# FourKeysKeyboard.net
KiCad netlist of a schematic drawn in Altium Designer
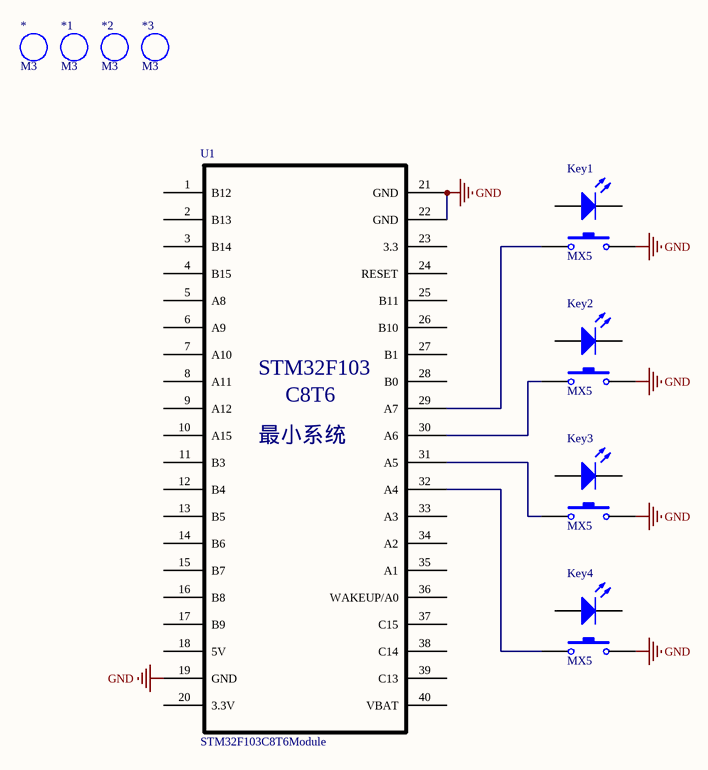
[diagram p0: FourKeysKeyboard.SchDoc]

(export (version "E")
  (design (tool "Eeschema 10.0.6"))
  (components
    (comp (ref "*")
      (value "M3")
      (footprint "M3 125X200")
      (description "铜柱孔")
      (fields (field (name "版权归属") "源创客"))
      (libsource (lib "未分类器件") (part "M3"))
    )
    (comp (ref "*1")
      (value "M3")
      (footprint "M3 125X200")
      (description "铜柱孔")
      (fields (field (name "版权归属") "源创客"))
      (libsource (lib "未分类器件") (part "M3"))
    )
    (comp (ref "*2")
      (value "M3")
      (footprint "M3 125X200")
      (description "铜柱孔")
      (fields (field (name "版权归属") "源创客"))
      (libsource (lib "未分类器件") (part "M3"))
    )
    (comp (ref "*3")
      (value "M3")
      (footprint "M3 125X200")
      (description "铜柱孔")
      (fields (field (name "版权归属") "源创客"))
      (libsource (lib "未分类器件") (part "M3"))
    )
    (comp (ref "Key1")
      (value "MX5")
      (footprint "LSW DIP-CHERRY")
      (libsource (lib "Multicoloredstone's_SW_and_Connector_Lib") (part "Cherry_Key_withLED"))
    )
    (comp (ref "Key2")
      (value "MX5")
      (footprint "LSW DIP-CHERRY")
      (libsource (lib "Multicoloredstone's_SW_and_Connector_Lib") (part "Cherry_Key_withLED"))
    )
    (comp (ref "Key3")
      (value "MX5")
      (footprint "LSW DIP-CHERRY")
      (libsource (lib "Multicoloredstone's_SW_and_Connector_Lib") (part "Cherry_Key_withLED"))
    )
    (comp (ref "Key4")
      (value "MX5")
      (footprint "LSW DIP-CHERRY")
      (libsource (lib "Multicoloredstone's_SW_and_Connector_Lib") (part "Cherry_Key_withLED"))
    )
    (comp (ref "U1")
      (value "STM32F103C8T6Module")
      (footprint "STM32F103C8T6_Module")
      (libsource (lib "Multicoloredstone's_Module_Lib") (part "STM32F103C8T6Module"))
    )
  )
  (nets
    (net (code "1") (name "GND") (class "Default")
      (node (ref "Key1") (pin "2") (pinfunction "2_2") (pintype "passive"))
      (node (ref "Key2") (pin "2") (pinfunction "2_2") (pintype "passive"))
      (node (ref "Key3") (pin "2") (pinfunction "2_2") (pintype "passive"))
      (node (ref "Key4") (pin "2") (pinfunction "2_2") (pintype "passive"))
      (node (ref "U1") (pin "19") (pinfunction "GND_19") (pintype "passive"))
      (node (ref "U1") (pin "21") (pinfunction "GND_21") (pintype "passive"))
      (node (ref "U1") (pin "22") (pinfunction "GND_22") (pintype "passive"))
    )
    (net (code "2") (name "Net-(U1-A4)") (class "Default")
      (node (ref "Key4") (pin "1") (pinfunction "1_1") (pintype "passive"))
      (node (ref "U1") (pin "32") (pinfunction "A4_32") (pintype "passive"))
    )
    (net (code "3") (name "Net-(U1-A5)") (class "Default")
      (node (ref "Key3") (pin "1") (pinfunction "1_1") (pintype "passive"))
      (node (ref "U1") (pin "31") (pinfunction "A5_31") (pintype "passive"))
    )
    (net (code "4") (name "Net-(U1-A6)") (class "Default")
      (node (ref "Key2") (pin "1") (pinfunction "1_1") (pintype "passive"))
      (node (ref "U1") (pin "30") (pinfunction "A6_30") (pintype "passive"))
    )
    (net (code "5") (name "Net-(U1-A7)") (class "Default")
      (node (ref "Key1") (pin "1") (pinfunction "1_1") (pintype "passive"))
      (node (ref "U1") (pin "29") (pinfunction "A7_29") (pintype "passive"))
    )
    (net (code "6") (name "unconnected-(Key1-PadA)") (class "Default")
      (node (ref "Key1") (pin "A") (pinfunction "A_A") (pintype "passive"))
    )
    (net (code "7") (name "unconnected-(Key1-PadK)") (class "Default")
      (node (ref "Key1") (pin "K") (pinfunction "K_K") (pintype "passive"))
    )
    (net (code "8") (name "unconnected-(Key2-PadA)") (class "Default")
      (node (ref "Key2") (pin "A") (pinfunction "A_A") (pintype "passive"))
    )
    (net (code "9") (name "unconnected-(Key2-PadK)") (class "Default")
      (node (ref "Key2") (pin "K") (pinfunction "K_K") (pintype "passive"))
    )
    (net (code "10") (name "unconnected-(Key3-PadA)") (class "Default")
      (node (ref "Key3") (pin "A") (pinfunction "A_A") (pintype "passive"))
    )
    (net (code "11") (name "unconnected-(Key3-PadK)") (class "Default")
      (node (ref "Key3") (pin "K") (pinfunction "K_K") (pintype "passive"))
    )
    (net (code "12") (name "unconnected-(Key4-PadA)") (class "Default")
      (node (ref "Key4") (pin "A") (pinfunction "A_A") (pintype "passive"))
    )
    (net (code "13") (name "unconnected-(Key4-PadK)") (class "Default")
      (node (ref "Key4") (pin "K") (pinfunction "K_K") (pintype "passive"))
    )
    (net (code "14") (name "unconnected-(U1-3.3-Pad23)") (class "Default")
      (node (ref "U1") (pin "23") (pinfunction "3.3_23") (pintype "passive"))
    )
    (net (code "15") (name "unconnected-(U1-3.3V-Pad20)") (class "Default")
      (node (ref "U1") (pin "20") (pinfunction "3.3V_20") (pintype "passive"))
    )
    (net (code "16") (name "unconnected-(U1-5V-Pad18)") (class "Default")
      (node (ref "U1") (pin "18") (pinfunction "5V_18") (pintype "passive"))
    )
    (net (code "17") (name "unconnected-(U1-A1-Pad35)") (class "Default")
      (node (ref "U1") (pin "35") (pinfunction "A1_35") (pintype "passive"))
    )
    (net (code "18") (name "unconnected-(U1-A2-Pad34)") (class "Default")
      (node (ref "U1") (pin "34") (pinfunction "A2_34") (pintype "passive"))
    )
    (net (code "19") (name "unconnected-(U1-A3-Pad33)") (class "Default")
      (node (ref "U1") (pin "33") (pinfunction "A3_33") (pintype "passive"))
    )
    (net (code "20") (name "unconnected-(U1-A8-Pad5)") (class "Default")
      (node (ref "U1") (pin "5") (pinfunction "A8_5") (pintype "passive"))
    )
    (net (code "21") (name "unconnected-(U1-A9-Pad6)") (class "Default")
      (node (ref "U1") (pin "6") (pinfunction "A9_6") (pintype "passive"))
    )
    (net (code "22") (name "unconnected-(U1-A10-Pad7)") (class "Default")
      (node (ref "U1") (pin "7") (pinfunction "A10_7") (pintype "passive"))
    )
    (net (code "23") (name "unconnected-(U1-A11-Pad8)") (class "Default")
      (node (ref "U1") (pin "8") (pinfunction "A11_8") (pintype "passive"))
    )
    (net (code "24") (name "unconnected-(U1-A12-Pad9)") (class "Default")
      (node (ref "U1") (pin "9") (pinfunction "A12_9") (pintype "passive"))
    )
    (net (code "25") (name "unconnected-(U1-A15-Pad10)") (class "Default")
      (node (ref "U1") (pin "10") (pinfunction "A15_10") (pintype "passive"))
    )
    (net (code "26") (name "unconnected-(U1-B0-Pad28)") (class "Default")
      (node (ref "U1") (pin "28") (pinfunction "B0_28") (pintype "passive"))
    )
    (net (code "27") (name "unconnected-(U1-B1-Pad27)") (class "Default")
      (node (ref "U1") (pin "27") (pinfunction "B1_27") (pintype "passive"))
    )
    (net (code "28") (name "unconnected-(U1-B3-Pad11)") (class "Default")
      (node (ref "U1") (pin "11") (pinfunction "B3_11") (pintype "passive"))
    )
    (net (code "29") (name "unconnected-(U1-B4-Pad12)") (class "Default")
      (node (ref "U1") (pin "12") (pinfunction "B4_12") (pintype "passive"))
    )
    (net (code "30") (name "unconnected-(U1-B5-Pad13)") (class "Default")
      (node (ref "U1") (pin "13") (pinfunction "B5_13") (pintype "passive"))
    )
    (net (code "31") (name "unconnected-(U1-B6-Pad14)") (class "Default")
      (node (ref "U1") (pin "14") (pinfunction "B6_14") (pintype "passive"))
    )
    (net (code "32") (name "unconnected-(U1-B7-Pad15)") (class "Default")
      (node (ref "U1") (pin "15") (pinfunction "B7_15") (pintype "passive"))
    )
    (net (code "33") (name "unconnected-(U1-B8-Pad16)") (class "Default")
      (node (ref "U1") (pin "16") (pinfunction "B8_16") (pintype "passive"))
    )
    (net (code "34") (name "unconnected-(U1-B9-Pad17)") (class "Default")
      (node (ref "U1") (pin "17") (pinfunction "B9_17") (pintype "passive"))
    )
    (net (code "35") (name "unconnected-(U1-B10-Pad26)") (class "Default")
      (node (ref "U1") (pin "26") (pinfunction "B10_26") (pintype "passive"))
    )
    (net (code "36") (name "unconnected-(U1-B11-Pad25)") (class "Default")
      (node (ref "U1") (pin "25") (pinfunction "B11_25") (pintype "passive"))
    )
    (net (code "37") (name "unconnected-(U1-B12-Pad1)") (class "Default")
      (node (ref "U1") (pin "1") (pinfunction "B12_1") (pintype "passive"))
    )
    (net (code "38") (name "unconnected-(U1-B13-Pad2)") (class "Default")
      (node (ref "U1") (pin "2") (pinfunction "B13_2") (pintype "passive"))
    )
    (net (code "39") (name "unconnected-(U1-B14-Pad3)") (class "Default")
      (node (ref "U1") (pin "3") (pinfunction "B14_3") (pintype "passive"))
    )
    (net (code "40") (name "unconnected-(U1-B15-Pad4)") (class "Default")
      (node (ref "U1") (pin "4") (pinfunction "B15_4") (pintype "passive"))
    )
    (net (code "41") (name "unconnected-(U1-C13-Pad39)") (class "Default")
      (node (ref "U1") (pin "39") (pinfunction "C13_39") (pintype "passive"))
    )
    (net (code "42") (name "unconnected-(U1-C14-Pad38)") (class "Default")
      (node (ref "U1") (pin "38") (pinfunction "C14_38") (pintype "passive"))
    )
    (net (code "43") (name "unconnected-(U1-C15-Pad37)") (class "Default")
      (node (ref "U1") (pin "37") (pinfunction "C15_37") (pintype "passive"))
    )
    (net (code "44") (name "unconnected-(U1-RESET-Pad24)") (class "Default")
      (node (ref "U1") (pin "24") (pinfunction "RESET_24") (pintype "passive"))
    )
    (net (code "45") (name "unconnected-(U1-VBAT-Pad40)") (class "Default")
      (node (ref "U1") (pin "40") (pinfunction "VBAT_40") (pintype "passive"))
    )
    (net (code "46") (name "unconnected-(U1-WAKEUP{slash}A0-Pad36)") (class "Default")
      (node (ref "U1") (pin "36") (pinfunction "WAKEUP/A0_36") (pintype "passive"))
    )
  )
)
